# FMC_DAC_PSU.net
KiCad netlist of a schematic drawn in Altium Designer
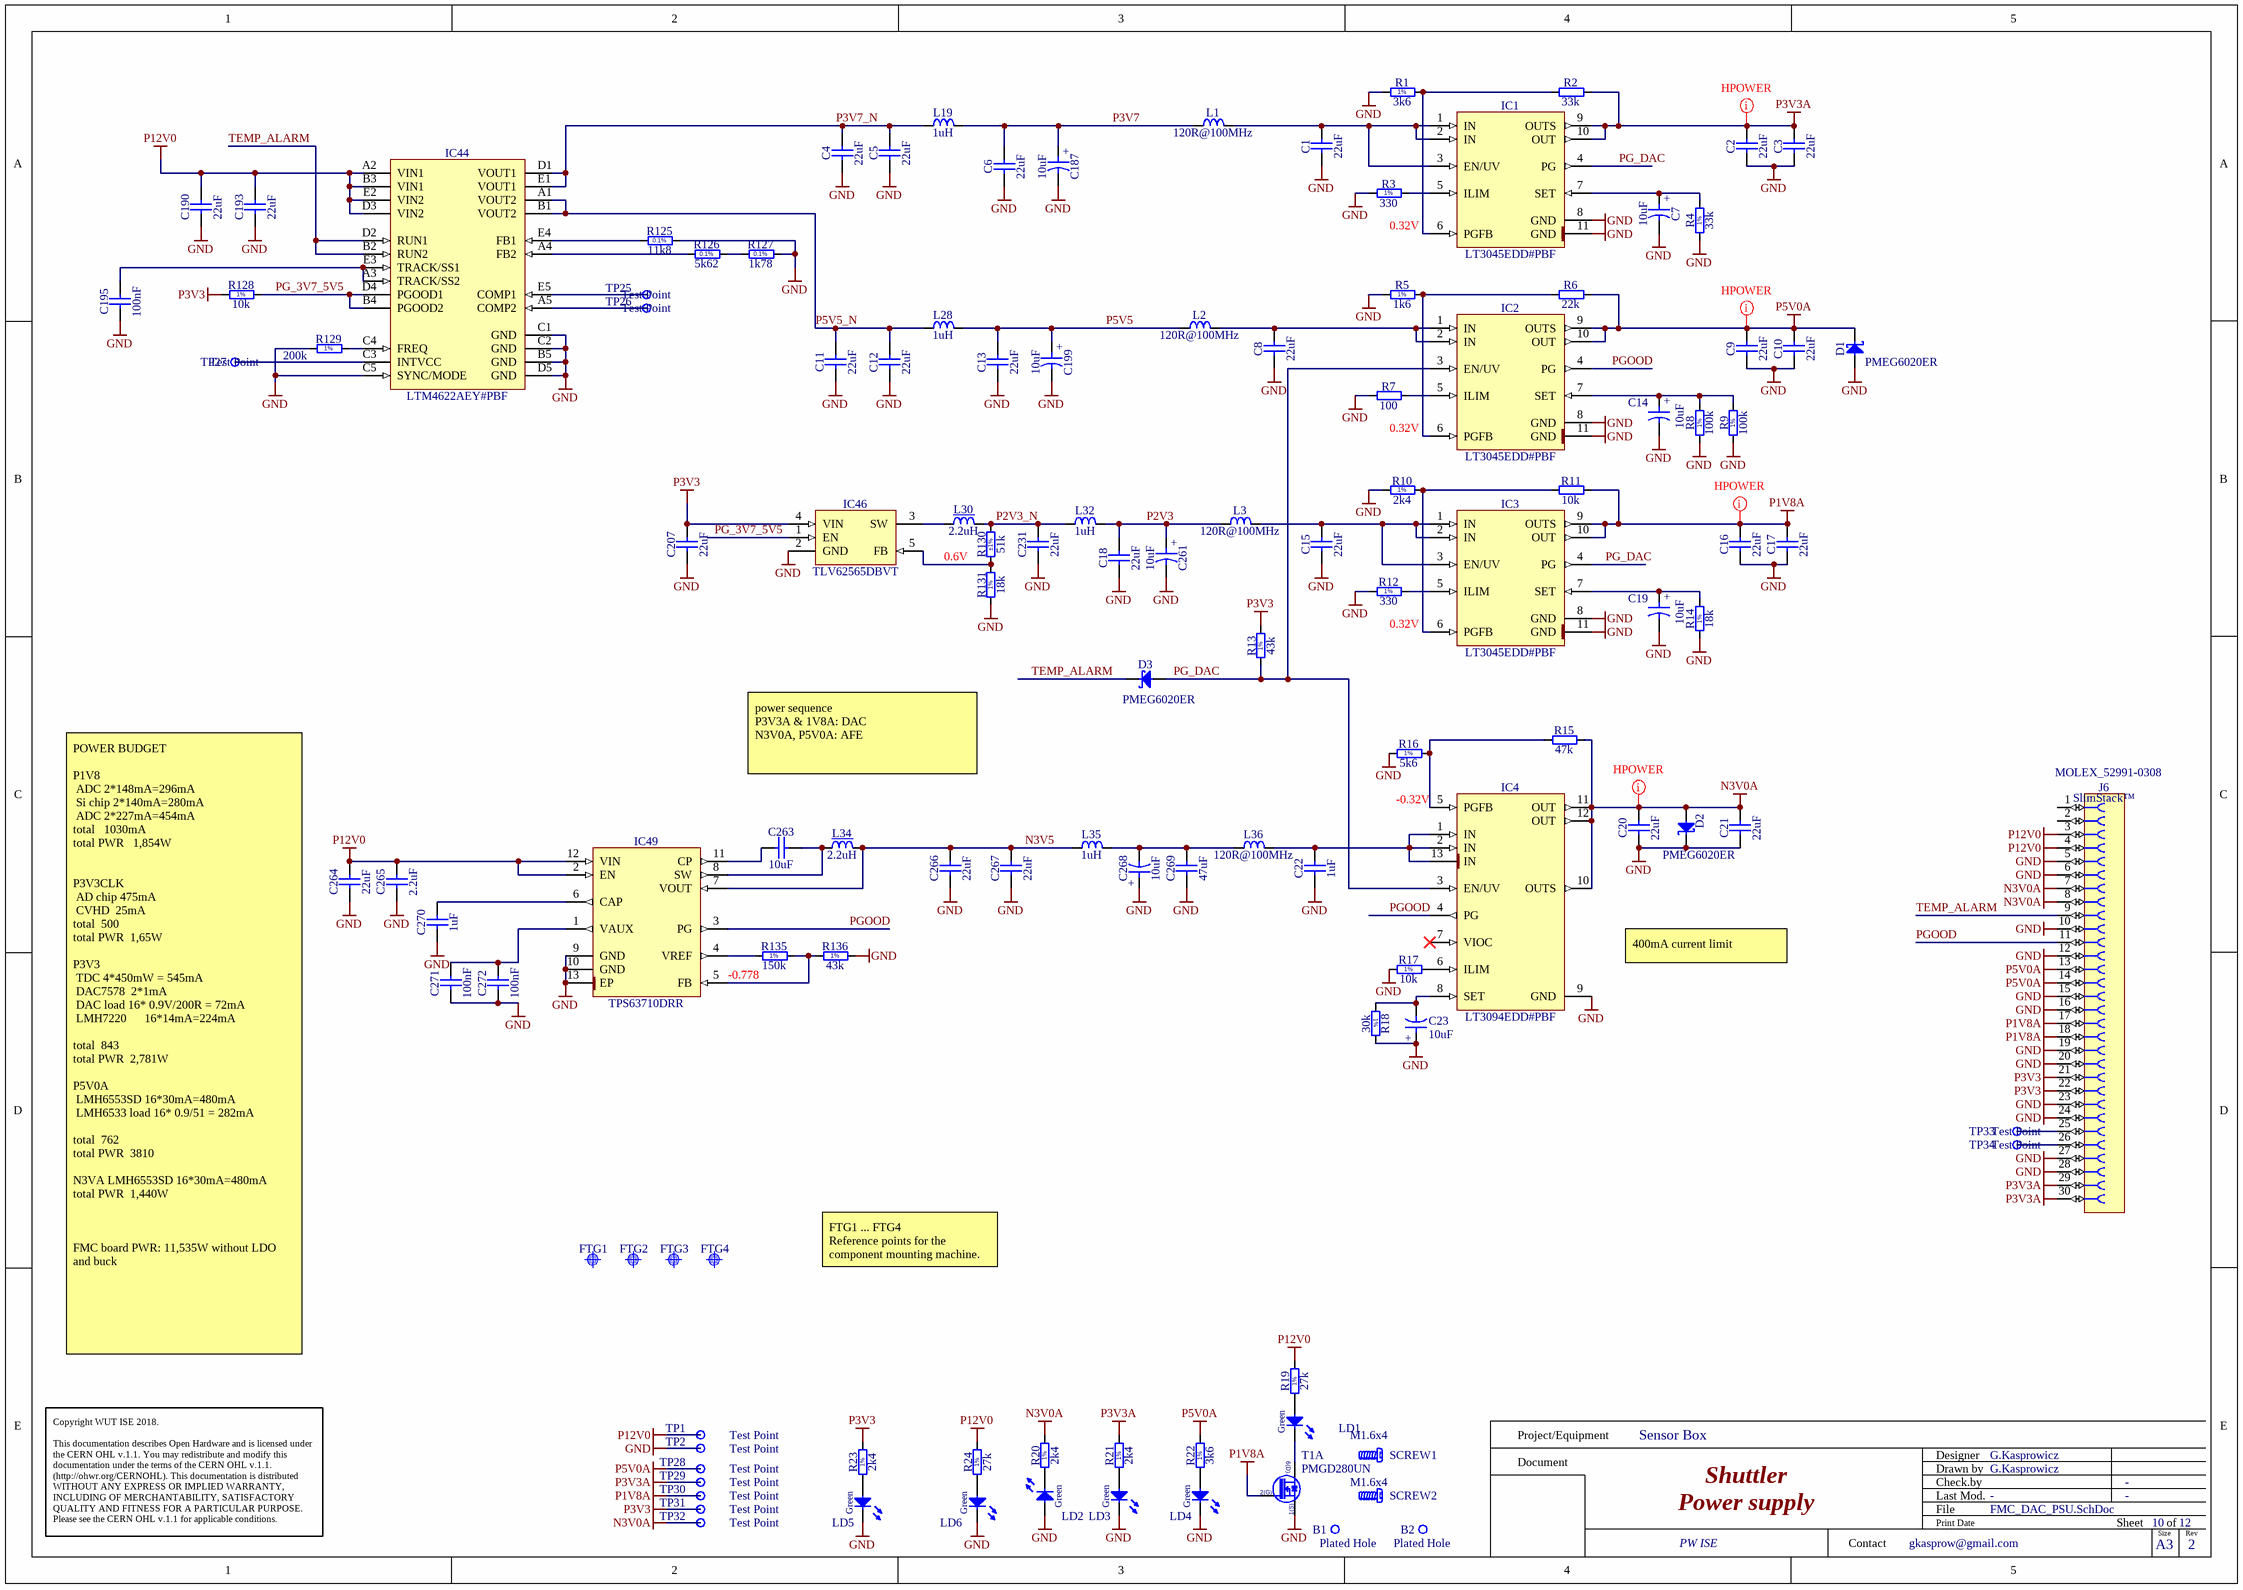
[diagram p0: FMC_DAC_PSU.SchDoc]

(export (version "E")
  (design (tool "Eeschema 10.0.6"))
  (components
    (comp (ref "B1")
      (value "Plated Hole")
      (footprint "c300h160")
      (description "Single Terminal Socket")
      (fields (field (name "PART NUMBER") "PLATED_HOLE1.6_PAD3.0") (field (name "AUTHOR") "CERN DEM JMW"))
      (libsource (lib "Eletro-mechanical") (part "Single Terminal Socket"))
    )
    (comp (ref "B2")
      (value "Plated Hole")
      (footprint "c300h160")
      (description "Single Terminal Socket")
      (fields (field (name "PART NUMBER") "PLATED_HOLE1.6_PAD3.0") (field (name "AUTHOR") "CERN DEM JMW"))
      (libsource (lib "Eletro-mechanical") (part "Single Terminal Socket"))
    )
    (comp (ref "C1")
      (value "22uF")
      (footprint "CAPC2012X135N")
      (description "Non-polarised capacitor")
      (fields
        (field (name "PART NUMBER") "CC0805_22UF_16V_10%_X5R")
        (field (name "VOLTAGE") "16V")
        (field (name "AUTHOR") "CERN DEM JLC")
      )
      (libsource (lib "Capacitors") (part "Capacitor - non polarized"))
    )
    (comp (ref "C2")
      (value "22uF")
      (footprint "CAPC2012X135N")
      (description "Non-polarised capacitor")
      (fields
        (field (name "PART NUMBER") "CC0805_22UF_16V_10%_X5R")
        (field (name "VOLTAGE") "16V")
        (field (name "AUTHOR") "CERN DEM JLC")
      )
      (libsource (lib "Capacitors") (part "Capacitor - non polarized"))
    )
    (comp (ref "C3")
      (value "22uF")
      (footprint "CAPC2012X135N")
      (description "Non-polarised capacitor")
      (fields
        (field (name "PART NUMBER") "CC0805_22UF_16V_10%_X5R")
        (field (name "VOLTAGE") "16V")
        (field (name "AUTHOR") "CERN DEM JLC")
      )
      (libsource (lib "Capacitors") (part "Capacitor - non polarized"))
    )
    (comp (ref "C4")
      (value "22uF")
      (footprint "CAPC2012X135N")
      (description "Non-polarised capacitor")
      (fields
        (field (name "PART NUMBER") "CC0805_22UF_16V_10%_X5R")
        (field (name "VOLTAGE") "16V")
        (field (name "AUTHOR") "CERN DEM JLC")
      )
      (libsource (lib "Capacitors") (part "Capacitor - non polarized"))
    )
    (comp (ref "C5")
      (value "22uF")
      (footprint "CAPC2012X135N")
      (description "Non-polarised capacitor")
      (fields
        (field (name "PART NUMBER") "CC0805_22UF_16V_10%_X5R")
        (field (name "VOLTAGE") "16V")
        (field (name "AUTHOR") "CERN DEM JLC")
      )
      (libsource (lib "Capacitors") (part "Capacitor - non polarized"))
    )
    (comp (ref "C6")
      (value "22uF")
      (footprint "CAPC2012X135N")
      (description "Non-polarised capacitor")
      (fields
        (field (name "PART NUMBER") "CC0805_22UF_16V_10%_X5R")
        (field (name "VOLTAGE") "16V")
        (field (name "AUTHOR") "CERN DEM JLC")
      )
      (libsource (lib "Capacitors") (part "Capacitor - non polarized"))
    )
    (comp (ref "C7")
      (value "10uF")
      (footprint "CAPMP3216X180N")
      (description "Polarised capacitor")
      (fields
        (field (name "PART NUMBER") "CTE3216-18_10UF_16V_20%_AVX_TCJ")
        (field (name "VOLTAGE") "16V")
        (field (name "AUTHOR") "CERN DEM JLC")
      )
      (libsource (lib "Capacitors") (part "Capacitor - polarized"))
    )
    (comp (ref "C8")
      (value "22uF")
      (footprint "CAPC2012X135N")
      (description "Non-polarised capacitor")
      (fields
        (field (name "PART NUMBER") "CC0805_22UF_16V_10%_X5R")
        (field (name "VOLTAGE") "16V")
        (field (name "AUTHOR") "CERN DEM JLC")
      )
      (libsource (lib "Capacitors") (part "Capacitor - non polarized"))
    )
    (comp (ref "C9")
      (value "22uF")
      (footprint "CAPC2012X135N")
      (description "Non-polarised capacitor")
      (fields
        (field (name "PART NUMBER") "CC0805_22UF_16V_10%_X5R")
        (field (name "VOLTAGE") "16V")
        (field (name "AUTHOR") "CERN DEM JLC")
      )
      (libsource (lib "Capacitors") (part "Capacitor - non polarized"))
    )
    (comp (ref "C10")
      (value "22uF")
      (footprint "CAPC2012X135N")
      (description "Non-polarised capacitor")
      (fields
        (field (name "PART NUMBER") "CC0805_22UF_16V_10%_X5R")
        (field (name "VOLTAGE") "16V")
        (field (name "AUTHOR") "CERN DEM JLC")
      )
      (libsource (lib "Capacitors") (part "Capacitor - non polarized"))
    )
    (comp (ref "C11")
      (value "22uF")
      (footprint "CAPC2012X135N")
      (description "Non-polarised capacitor")
      (fields
        (field (name "PART NUMBER") "CC0805_22UF_16V_10%_X5R")
        (field (name "VOLTAGE") "16V")
        (field (name "AUTHOR") "CERN DEM JLC")
      )
      (libsource (lib "Capacitors") (part "Capacitor - non polarized"))
    )
    (comp (ref "C12")
      (value "22uF")
      (footprint "CAPC2012X135N")
      (description "Non-polarised capacitor")
      (fields
        (field (name "PART NUMBER") "CC0805_22UF_16V_10%_X5R")
        (field (name "VOLTAGE") "16V")
        (field (name "AUTHOR") "CERN DEM JLC")
      )
      (libsource (lib "Capacitors") (part "Capacitor - non polarized"))
    )
    (comp (ref "C13")
      (value "22uF")
      (footprint "CAPC2012X135N")
      (description "Non-polarised capacitor")
      (fields
        (field (name "PART NUMBER") "CC0805_22UF_16V_10%_X5R")
        (field (name "VOLTAGE") "16V")
        (field (name "AUTHOR") "CERN DEM JLC")
      )
      (libsource (lib "Capacitors") (part "Capacitor - non polarized"))
    )
    (comp (ref "C14")
      (value "10uF")
      (footprint "CAPMP3216X180N")
      (description "Polarised capacitor")
      (fields
        (field (name "PART NUMBER") "CTE3216-18_10UF_16V_20%_AVX_TCJ")
        (field (name "VOLTAGE") "16V")
        (field (name "AUTHOR") "CERN DEM JLC")
      )
      (libsource (lib "Capacitors") (part "Capacitor - polarized"))
    )
    (comp (ref "C15")
      (value "22uF")
      (footprint "CAPC2012X135N")
      (description "Non-polarised capacitor")
      (fields
        (field (name "PART NUMBER") "CC0805_22UF_16V_10%_X5R")
        (field (name "VOLTAGE") "16V")
        (field (name "AUTHOR") "CERN DEM JLC")
      )
      (libsource (lib "Capacitors") (part "Capacitor - non polarized"))
    )
    (comp (ref "C16")
      (value "22uF")
      (footprint "CAPC2012X135N")
      (description "Non-polarised capacitor")
      (fields
        (field (name "PART NUMBER") "CC0805_22UF_16V_10%_X5R")
        (field (name "VOLTAGE") "16V")
        (field (name "AUTHOR") "CERN DEM JLC")
      )
      (libsource (lib "Capacitors") (part "Capacitor - non polarized"))
    )
    (comp (ref "C17")
      (value "22uF")
      (footprint "CAPC2012X135N")
      (description "Non-polarised capacitor")
      (fields
        (field (name "PART NUMBER") "CC0805_22UF_16V_10%_X5R")
        (field (name "VOLTAGE") "16V")
        (field (name "AUTHOR") "CERN DEM JLC")
      )
      (libsource (lib "Capacitors") (part "Capacitor - non polarized"))
    )
    (comp (ref "C18")
      (value "22uF")
      (footprint "CAPC2012X135N")
      (description "Non-polarised capacitor")
      (fields
        (field (name "PART NUMBER") "CC0805_22UF_16V_10%_X5R")
        (field (name "VOLTAGE") "16V")
        (field (name "AUTHOR") "CERN DEM JLC")
      )
      (libsource (lib "Capacitors") (part "Capacitor - non polarized"))
    )
    (comp (ref "C19")
      (value "10uF")
      (footprint "CAPMP3216X180N")
      (description "Polarised capacitor")
      (fields
        (field (name "PART NUMBER") "CTE3216-18_10UF_16V_20%_AVX_TCJ")
        (field (name "VOLTAGE") "16V")
        (field (name "AUTHOR") "CERN DEM JLC")
      )
      (libsource (lib "Capacitors") (part "Capacitor - polarized"))
    )
    (comp (ref "C20")
      (value "22uF")
      (footprint "CAPC2012X135N")
      (description "Non-polarised capacitor")
      (fields
        (field (name "PART NUMBER") "CC0805_22UF_16V_10%_X5R")
        (field (name "VOLTAGE") "16V")
        (field (name "AUTHOR") "CERN DEM JLC")
      )
      (libsource (lib "Capacitors") (part "Capacitor - non polarized"))
    )
    (comp (ref "C21")
      (value "22uF")
      (footprint "CAPC2012X135N")
      (description "Non-polarised capacitor")
      (fields
        (field (name "PART NUMBER") "CC0805_22UF_16V_10%_X5R")
        (field (name "VOLTAGE") "16V")
        (field (name "AUTHOR") "CERN DEM JLC")
      )
      (libsource (lib "Capacitors") (part "Capacitor - non polarized"))
    )
    (comp (ref "C22")
      (value "1uF")
      (footprint "CAPC1608X87N")
      (description "Non-polarised capacitor")
      (fields
        (field (name "PART NUMBER") "CC0603_1UF_25V_10%_X7R")
        (field (name "VOLTAGE") "25V")
        (field (name "AUTHOR") "CERN DEM JLC")
      )
      (libsource (lib "Capacitors") (part "Capacitor - non polarized"))
    )
    (comp (ref "C23")
      (value "10uF")
      (footprint "CAPMP3216X180N")
      (description "Polarised capacitor")
      (fields
        (field (name "PART NUMBER") "CTE3216-18_10UF_16V_20%_AVX_TCJ")
        (field (name "VOLTAGE") "16V")
        (field (name "AUTHOR") "CERN DEM JLC")
      )
      (libsource (lib "Capacitors") (part "Capacitor - polarized"))
    )
    (comp (ref "C187")
      (value "10uF")
      (footprint "CAPMP3216X180N")
      (description "Polarised capacitor")
      (fields
        (field (name "PART NUMBER") "CTE3216-18_10UF_10V_10%_LESR1800")
        (field (name "VOLTAGE") "10V")
        (field (name "AUTHOR") "CERN DEM JLC")
      )
      (libsource (lib "Capacitors") (part "Capacitor - polarized"))
    )
    (comp (ref "C190")
      (value "22uF")
      (footprint "CAPC2012X135N")
      (description "Non-polarised capacitor")
      (fields
        (field (name "PART NUMBER") "CC0805_22UF_16V_10%_X5R")
        (field (name "VOLTAGE") "16V")
        (field (name "AUTHOR") "CERN DEM JLC")
      )
      (libsource (lib "Capacitors") (part "Capacitor - non polarized"))
    )
    (comp (ref "C193")
      (value "22uF")
      (footprint "CAPC2012X135N")
      (description "Non-polarised capacitor")
      (fields
        (field (name "PART NUMBER") "CC0805_22UF_16V_10%_X5R")
        (field (name "VOLTAGE") "16V")
        (field (name "AUTHOR") "CERN DEM JLC")
      )
      (libsource (lib "Capacitors") (part "Capacitor - non polarized"))
    )
    (comp (ref "C195")
      (value "100nF")
      (footprint "CAPC1005X55N")
      (description "Non-polarised capacitor")
      (fields
        (field (name "PART NUMBER") "CC0402_100NF_16V_10%_X5R")
        (field (name "VOLTAGE") "16V")
        (field (name "AUTHOR") "CERN DEM JLC")
      )
      (libsource (lib "Capacitors") (part "Capacitor - non polarized"))
    )
    (comp (ref "C199")
      (value "10uF")
      (footprint "CAPMP3216X180N")
      (description "Polarised capacitor")
      (fields
        (field (name "PART NUMBER") "CTE3216-18_10UF_10V_10%_LESR1800")
        (field (name "VOLTAGE") "10V")
        (field (name "AUTHOR") "CERN DEM JLC")
      )
      (libsource (lib "Capacitors") (part "Capacitor - polarized"))
    )
    (comp (ref "C207")
      (value "22uF")
      (footprint "CAPC2012X135N")
      (description "Non-polarised capacitor")
      (fields
        (field (name "PART NUMBER") "CC0805_22UF_16V_10%_X5R")
        (field (name "VOLTAGE") "16V")
        (field (name "AUTHOR") "CERN DEM JLC")
      )
      (libsource (lib "Capacitors") (part "Capacitor - non polarized"))
    )
    (comp (ref "C231")
      (value "22uF")
      (footprint "CAPC2012X135N")
      (description "Non-polarised capacitor")
      (fields
        (field (name "PART NUMBER") "CC0805_22UF_16V_10%_X5R")
        (field (name "VOLTAGE") "16V")
        (field (name "AUTHOR") "CERN DEM JLC")
      )
      (libsource (lib "Capacitors") (part "Capacitor - non polarized"))
    )
    (comp (ref "C261")
      (value "10uF")
      (footprint "CAPMP3216X180N")
      (description "Polarised capacitor")
      (fields
        (field (name "PART NUMBER") "CTE3216-18_10UF_10V_10%_LESR1800")
        (field (name "VOLTAGE") "10V")
        (field (name "AUTHOR") "CERN DEM JLC")
      )
      (libsource (lib "Capacitors") (part "Capacitor - polarized"))
    )
    (comp (ref "C263")
      (value "10uF")
      (footprint "CAPC2012X135N")
      (description "Non-polarised capacitor")
      (fields
        (field (name "PART NUMBER") "CC0805_10UF_16V_10%_X5R")
        (field (name "VOLTAGE") "16V")
        (field (name "AUTHOR") "CERN DEM JLC")
      )
      (libsource (lib "Capacitors") (part "Capacitor - non polarized"))
    )
    (comp (ref "C264")
      (value "22uF")
      (footprint "CAPC2012X135N")
      (description "Non-polarised capacitor")
      (fields
        (field (name "PART NUMBER") "CC0805_22UF_16V_10%_X5R")
        (field (name "VOLTAGE") "16V")
        (field (name "AUTHOR") "CERN DEM JLC")
      )
      (libsource (lib "Capacitors") (part "Capacitor - non polarized"))
    )
    (comp (ref "C265")
      (value "2.2uF")
      (footprint "CAPC1608X87N")
      (description "Non-polarised capacitor")
      (fields
        (field (name "PART NUMBER") "CC0603_2.2UF_16V_10%_X5R")
        (field (name "VOLTAGE") "16V")
        (field (name "AUTHOR") "CERN DEM JLC")
      )
      (libsource (lib "Capacitors") (part "Capacitor - non polarized"))
    )
    (comp (ref "C266")
      (value "22uF")
      (footprint "CAPC2012X135N")
      (description "Non-polarised capacitor")
      (fields
        (field (name "PART NUMBER") "CC0805_22UF_16V_10%_X5R")
        (field (name "VOLTAGE") "16V")
        (field (name "AUTHOR") "CERN DEM JLC")
      )
      (libsource (lib "Capacitors") (part "Capacitor - non polarized"))
    )
    (comp (ref "C267")
      (value "22uF")
      (footprint "CAPC2012X135N")
      (description "Non-polarised capacitor")
      (fields
        (field (name "PART NUMBER") "CC0805_22UF_16V_10%_X5R")
        (field (name "VOLTAGE") "16V")
        (field (name "AUTHOR") "CERN DEM JLC")
      )
      (libsource (lib "Capacitors") (part "Capacitor - non polarized"))
    )
    (comp (ref "C268")
      (value "10uF")
      (footprint "CAPMP3216X180N")
      (description "Polarised capacitor")
      (fields
        (field (name "PART NUMBER") "CTE3216-18_10UF_10V_10%_LESR1800")
        (field (name "VOLTAGE") "10V")
        (field (name "AUTHOR") "CERN DEM JLC")
      )
      (libsource (lib "Capacitors") (part "Capacitor - polarized"))
    )
    (comp (ref "C269")
      (value "47uF")
      (footprint "CAPC2012X140N")
      (description "Non-polarised capacitor")
      (fields
        (field (name "PART NUMBER") "CC0805_47UF_6.3V_20%_X5R")
        (field (name "VOLTAGE") "6.3V")
        (field (name "AUTHOR") "CERN DEM JLC")
      )
      (libsource (lib "Capacitors") (part "Capacitor - non polarized"))
    )
    (comp (ref "C270")
      (value "1uF")
      (footprint "CAPC1608X87N")
      (description "Non-polarised capacitor")
      (fields
        (field (name "PART NUMBER") "CC0603_1UF_16V_10%_X7R")
        (field (name "VOLTAGE") "16V")
        (field (name "AUTHOR") "CERN DEM JLC")
      )
      (libsource (lib "Capacitors") (part "Capacitor - non polarized"))
    )
    (comp (ref "C271")
      (value "100nF")
      (footprint "CAPC1005X55N")
      (description "Non-polarised capacitor")
      (fields
        (field (name "PART NUMBER") "CC0402_100NF_16V_10%_X5R")
        (field (name "VOLTAGE") "16V")
        (field (name "AUTHOR") "CERN DEM JLC")
      )
      (libsource (lib "Capacitors") (part "Capacitor - non polarized"))
    )
    (comp (ref "C272")
      (value "100nF")
      (footprint "CAPC1005X55N")
      (description "Non-polarised capacitor")
      (fields
        (field (name "PART NUMBER") "CC0402_100NF_16V_10%_X5R")
        (field (name "VOLTAGE") "16V")
        (field (name "AUTHOR") "CERN DEM JLC")
      )
      (libsource (lib "Capacitors") (part "Capacitor - non polarized"))
    )
    (comp (ref "D1")
      (value "PMEG6020ER")
      (footprint "SODFL3517X110N")
      (description "Schottky Diode")
      (fields
        (field (name "VOLTAGE") "60V")
        (field (name "POWER") "2A")
        (field (name "AUTHOR") "CERN DEM JMW")
      )
      (libsource (lib "ICs And Semiconductors") (part "Diode Schottky"))
    )
    (comp (ref "D2")
      (value "PMEG6020ER")
      (footprint "SODFL3517X110N")
      (description "Schottky Diode")
      (fields
        (field (name "VOLTAGE") "60V")
        (field (name "POWER") "2A")
        (field (name "AUTHOR") "CERN DEM JMW")
      )
      (libsource (lib "ICs And Semiconductors") (part "Diode Schottky"))
    )
    (comp (ref "D3")
      (value "PMEG6020ER")
      (footprint "SODFL3517X110N")
      (description "Schottky Diode")
      (fields
        (field (name "VOLTAGE") "60V")
        (field (name "POWER") "2A")
        (field (name "AUTHOR") "CERN DEM JMW")
      )
      (libsource (lib "ICs And Semiconductors") (part "Diode Schottky"))
    )
    (comp (ref "FTG1")
      (value "Use only in PCB")
      (footprint "FIDUCIAL_TOP_S100-200")
      (description "Fiducial Target")
      (fields (field (name "PART NUMBER") "FIDUCIAL_TARGET_S100-200") (field (name "AUTHOR") "CERN DEM JLC"))
      (libsource (lib "Eletro-mechanical") (part "Fiducial Target"))
    )
    (comp (ref "FTG2")
      (value "Use only in PCB")
      (footprint "FIDUCIAL_TOP_C100-200")
      (description "Fiducial Target")
      (fields (field (name "PART NUMBER") "FIDUCIAL_TARGET_C100-200") (field (name "AUTHOR") "CERN DEM JLC"))
      (libsource (lib "Eletro-mechanical") (part "Fiducial Target"))
    )
    (comp (ref "FTG3")
      (value "Use only in PCB")
      (footprint "FIDUCIAL_TOP_S100-200")
      (description "Fiducial Target")
      (fields (field (name "PART NUMBER") "FIDUCIAL_TARGET_S100-200") (field (name "AUTHOR") "CERN DEM JLC"))
      (libsource (lib "Eletro-mechanical") (part "Fiducial Target"))
    )
    (comp (ref "FTG4")
      (value "Use only in PCB")
      (footprint "FIDUCIAL_TOP_C100-200")
      (description "Fiducial Target")
      (fields (field (name "PART NUMBER") "FIDUCIAL_TARGET_C100-200") (field (name "AUTHOR") "CERN DEM JLC"))
      (libsource (lib "Eletro-mechanical") (part "Fiducial Target"))
    )
    (comp (ref "IC1")
      (value "LT3045EDD#PBF")
      (footprint "SON50P300X300X80-11N-R175X248")
      (description "20V, 500mA, Ultralow Noise, Ultrahigh PSRR Linear Regulator")
      (fields (field (name "MANUFACTURER") "LINEAR TECHNOLOGY") (field (name "AUTHOR") "CERN DEM JLC"))
      (libsource (lib "ICs And Semiconductors") (part "LT3045EDD"))
    )
    (comp (ref "IC2")
      (value "LT3045EDD#PBF")
      (footprint "SON50P300X300X80-11N-R175X248")
      (description "20V, 500mA, Ultralow Noise, Ultrahigh PSRR Linear Regulator")
      (fields (field (name "MANUFACTURER") "LINEAR TECHNOLOGY") (field (name "AUTHOR") "CERN DEM JLC"))
      (libsource (lib "ICs And Semiconductors") (part "LT3045EDD"))
    )
    (comp (ref "IC3")
      (value "LT3045EDD#PBF")
      (footprint "SON50P300X300X80-11N-R175X248")
      (description "20V, 500mA, Ultralow Noise, Ultrahigh PSRR Linear Regulator")
      (fields (field (name "MANUFACTURER") "LINEAR TECHNOLOGY") (field (name "AUTHOR") "CERN DEM JLC"))
      (libsource (lib "ICs And Semiconductors") (part "LT3045EDD"))
    )
    (comp (ref "IC4")
      (value "LT3094EDD#PBF")
      (footprint "SON45P300X300X80-13N-R175X248")
      (description "-20V, 500mA, Ultralow Noise, Ultrahigh PSRR Negative Linear Regulator")
      (fields (field (name "MANUFACTURER") "LINEAR TECHNOLOGY") (field (name "AUTHOR") "CERN DEM JLC"))
      (libsource (lib "ICs And Semiconductors") (part "LT3094"))
    )
    (comp (ref "IC44")
      (value "LTM4622AEY#PBF")
      (footprint "BGA25C127P5X5_625X625X262")
      (description "3.6V-20V To 1.5V-12V, Dual 2A or Single 4A  Ultrathin Step-Down DC/DC µModule Regulator")
      (fields (field (name "MANUFACTURER") "LINEAR TECHNOLOGY") (field (name "AUTHOR") "CERN DEM MR"))
      (libsource (lib "ICs And Semiconductors") (part "LTM4622A"))
    )
    (comp (ref "IC46")
      (value "TLV62565DBVT")
      (footprint "SOT95P280X145-5N")
      (description "1.5A High Efficiency Step-Down Converter, Adjustable Output Voltage")
      (fields (field (name "MANUFACTURER") "TEXAS INSTRUMENTS") (field (name "AUTHOR") "CERN DEM JMW"))
      (libsource (lib "ICs And Semiconductors") (part "TLV62565"))
    )
    (comp (ref "IC49")
      (value "TPS63710DRR")
      (footprint "SON50P300X300X80-13N-R160X260")
      (description "-1 to -5.5VDC, 1A Output, Low Noise Synchronous Inverting Buck Converter")
      (fields (field (name "MANUFACTURER") "TEXAS INSTRUMENTS") (field (name "AUTHOR") "CERN DEM BC"))
      (libsource (lib "ICs And Semiconductors") (part "TPS63710"))
    )
    (comp (ref "J6")
      (value "SlimStack™")
      (footprint "MOLEX_52991-0308")
      (description "Connector 30 Female")
      (fields
        (field (name "PART NUMBER") "MOLEX_52991-0308")
        (field (name "MANUFACTURER") "MOLEX")
        (field (name "MANUFACTURER PART NUMBER") "52991-0308")
        (field (name "AUTHOR") "CERN DEM JLC")
      )
      (libsource (lib "Connectors") (part "Connector 30 Female"))
    )
    (comp (ref "L1")
      (value "120R@100MHz")
      (footprint "INDC1608X65N")
      (description "Inductor")
      (fields
        (field (name "PART NUMBER") "IND0603_MURATA_BLM18SG121TN1D")
        (field (name "POWER") "3A")
        (field (name "AUTHOR") "CERN DEM JLC")
      )
      (libsource (lib "Inductors & Transformers") (part "Inductor"))
    )
    (comp (ref "L2")
      (value "120R@100MHz")
      (footprint "INDC1608X65N")
      (description "Inductor")
      (fields
        (field (name "PART NUMBER") "IND0603_MURATA_BLM18SG121TN1D")
        (field (name "POWER") "3A")
        (field (name "AUTHOR") "CERN DEM JLC")
      )
      (libsource (lib "Inductors & Transformers") (part "Inductor"))
    )
    (comp (ref "L3")
      (value "120R@100MHz")
      (footprint "INDC1608X65N")
      (description "Inductor")
      (fields
        (field (name "PART NUMBER") "IND0603_MURATA_BLM18SG121TN1D")
        (field (name "POWER") "3A")
        (field (name "AUTHOR") "CERN DEM JLC")
      )
      (libsource (lib "Inductors & Transformers") (part "Inductor"))
    )
    (comp (ref "L19")
      (value "1uH")
      (footprint "INDC2620X100N")
      (description "Inductor")
      (fields
        (field (name "PART NUMBER") "IND1008_1UH_20%_WURTH_74479787210B")
        (field (name "POWER") "1.95A")
        (field (name "AUTHOR") "CERN DEM JLC")
      )
      (libsource (lib "Inductors & Transformers") (part "Inductor"))
    )
    (comp (ref "L28")
      (value "1uH")
      (footprint "INDC2620X100N")
      (description "Inductor")
      (fields
        (field (name "PART NUMBER") "IND1008_1UH_20%_WURTH_74479787210B")
        (field (name "POWER") "1.95A")
        (field (name "AUTHOR") "CERN DEM JLC")
      )
      (libsource (lib "Inductors & Transformers") (part "Inductor"))
    )
    (comp (ref "L30")
      (value "2.2uH")
      (footprint "IND_WURTH_WE-TPC_4828")
      (description "Inductor With Core")
      (fields
        (field (name "PART NUMBER") "IND_2.2UH_30%_WURTH_WE-TPC_7440430022")
        (field (name "POWER") "2.5A")
        (field (name "AUTHOR") "CERN DEM JLC")
      )
      (libsource (lib "Inductors & Transformers") (part "Inductor With Magnetic core"))
    )
    (comp (ref "L32")
      (value "1uH")
      (footprint "INDC2620X100N")
      (description "Inductor")
      (fields
        (field (name "PART NUMBER") "IND1008_1UH_20%_WURTH_74479787210B")
        (field (name "POWER") "1.95A")
        (field (name "AUTHOR") "CERN DEM JLC")
      )
      (libsource (lib "Inductors & Transformers") (part "Inductor"))
    )
    (comp (ref "L34")
      (value "2.2uH")
      (footprint "IND_WURTH_WE-TPC_4828")
      (description "Inductor With Core")
      (fields
        (field (name "PART NUMBER") "IND_2.2UH_30%_WURTH_WE-TPC_7440430022")
        (field (name "POWER") "2.5A")
        (field (name "AUTHOR") "CERN DEM JLC")
      )
      (libsource (lib "Inductors & Transformers") (part "Inductor With Magnetic core"))
    )
    (comp (ref "L35")
      (value "1uH")
      (footprint "INDC2620X100N")
      (description "Inductor")
      (fields
        (field (name "PART NUMBER") "IND1008_1UH_20%_WURTH_74479787210B")
        (field (name "POWER") "1.95A")
        (field (name "AUTHOR") "CERN DEM JLC")
      )
      (libsource (lib "Inductors & Transformers") (part "Inductor"))
    )
    (comp (ref "L36")
      (value "120R@100MHz")
      (footprint "INDC1608X65N")
      (description "Inductor")
      (fields
        (field (name "PART NUMBER") "IND0603_MURATA_BLM18SG121TN1D")
        (field (name "POWER") "3A")
        (field (name "AUTHOR") "CERN DEM JLC")
      )
      (libsource (lib "Inductors & Transformers") (part "Inductor"))
    )
    (comp (ref "LD1")
      (value "Green")
      (footprint "LED_KINGBRIGHT_KPH-1608CGCK")
      (description "LED Green 1C 2A")
      (fields
        (field (name "PART NUMBER") "LED_KINGBRIGHT_KPH-1608CGCK")
        (field (name "MANUFACTURER") "KINGBRIGHT")
        (field (name "AUTHOR") "CERN DEM JLC")
      )
      (libsource (lib "ICs And Semiconductors") (part "LED Green 1C 2A"))
    )
    (comp (ref "LD2")
      (value "Green")
      (footprint "LED_KINGBRIGHT_KPH-1608CGCK")
      (description "LED Green 1C 2A")
      (fields
        (field (name "PART NUMBER") "LED_KINGBRIGHT_KPH-1608CGCK")
        (field (name "MANUFACTURER") "KINGBRIGHT")
        (field (name "AUTHOR") "CERN DEM JLC")
      )
      (libsource (lib "ICs And Semiconductors") (part "LED Green 1C 2A"))
    )
    (comp (ref "LD3")
      (value "Green")
      (footprint "LED_KINGBRIGHT_KPH-1608CGCK")
      (description "LED Green 1C 2A")
      (fields
        (field (name "PART NUMBER") "LED_KINGBRIGHT_KPH-1608CGCK")
        (field (name "MANUFACTURER") "KINGBRIGHT")
        (field (name "AUTHOR") "CERN DEM JLC")
      )
      (libsource (lib "ICs And Semiconductors") (part "LED Green 1C 2A"))
    )
    (comp (ref "LD4")
      (value "Green")
      (footprint "LED_KINGBRIGHT_KPH-1608CGCK")
      (description "LED Green 1C 2A")
      (fields
        (field (name "PART NUMBER") "LED_KINGBRIGHT_KPH-1608CGCK")
        (field (name "MANUFACTURER") "KINGBRIGHT")
        (field (name "AUTHOR") "CERN DEM JLC")
      )
      (libsource (lib "ICs And Semiconductors") (part "LED Green 1C 2A"))
    )
    (comp (ref "LD5")
      (value "Green")
      (footprint "LED_KINGBRIGHT_KPH-1608CGCK")
      (description "LED Green 1C 2A")
      (fields
        (field (name "PART NUMBER") "LED_KINGBRIGHT_KPH-1608CGCK")
        (field (name "MANUFACTURER") "KINGBRIGHT")
        (field (name "AUTHOR") "CERN DEM JLC")
      )
      (libsource (lib "ICs And Semiconductors") (part "LED Green 1C 2A"))
    )
    (comp (ref "LD6")
      (value "Green")
      (footprint "LED_KINGBRIGHT_KPH-1608CGCK")
      (description "LED Green 1C 2A")
      (fields
        (field (name "PART NUMBER") "LED_KINGBRIGHT_KPH-1608CGCK")
        (field (name "MANUFACTURER") "KINGBRIGHT")
        (field (name "AUTHOR") "CERN DEM JLC")
      )
      (libsource (lib "ICs And Semiconductors") (part "LED Green 1C 2A"))
    )
    (comp (ref "R1")
      (value "3k6")
      (footprint "RESC1005X40N")
      (description "Resistor - 1%")
      (fields
        (field (name "PART NUMBER") "R0402_3K6_1%_0.0625W_100PPM")
        (field (name "POWER") "0.0625W")
        (field (name "AUTHOR") "CERN DEM JLC")
      )
      (libsource (lib "Resistors") (part "Resistor - 1%"))
    )
    (comp (ref "R2")
      (value "33k")
      (footprint "RESC1005X40N")
      (description "Resistor - 1%")
      (fields
        (field (name "PART NUMBER") "R0402_33K_1%_0.0625W_100PPM")
        (field (name "POWER") "0.0625W")
        (field (name "AUTHOR") "CERN DEM JLC")
      )
      (libsource (lib "Resistors") (part "Resistor - 1%"))
    )
    (comp (ref "R3")
      (value "330")
      (footprint "RESC1005X40N")
      (description "Resistor - 1%")
      (fields
        (field (name "PART NUMBER") "R0402_330R_1%_0.0625W_100PPM")
        (field (name "POWER") "0.0625W")
        (field (name "AUTHOR") "CERN DEM JLC")
      )
      (libsource (lib "Resistors") (part "Resistor - 1%"))
    )
    (comp (ref "R4")
      (value "33k")
      (footprint "RESC1608X55N")
      (description "Resistor - 1%")
      (fields
        (field (name "PART NUMBER") "R0603_33K_1%_0.1W_100PPM")
        (field (name "POWER") "0.1W")
        (field (name "AUTHOR") "CERN DEM JLC")
      )
      (libsource (lib "Resistors") (part "Resistor - 1%"))
    )
    (comp (ref "R5")
      (value "1k6")
      (footprint "RESC1005X40N")
      (description "Resistor - 1%")
      (fields
        (field (name "PART NUMBER") "R0402_1K6_1%_0.0625W_100PPM")
        (field (name "POWER") "0.0625W")
        (field (name "AUTHOR") "CERN DEM JLC")
      )
      (libsource (lib "Resistors") (part "Resistor - 1%"))
    )
    (comp (ref "R6")
      (value "22k")
      (footprint "RESC1005X40N")
      (description "Resistor - 1%")
      (fields
        (field (name "PART NUMBER") "R0402_22K_1%_0.0625W_100PPM")
        (field (name "POWER") "0.0625W")
        (field (name "AUTHOR") "CERN DEM JLC")
      )
      (libsource (lib "Resistors") (part "Resistor - 1%"))
    )
    (comp (ref "R7")
      (value "100")
      (footprint "RESC1005X40N")
      (description "Resistor - 1%")
      (fields
        (field (name "PART NUMBER") "R0402_100R_1%_0.0625W_100PPM")
        (field (name "POWER") "0.0625W")
        (field (name "AUTHOR") "CERN DEM JLC")
      )
      (libsource (lib "Resistors") (part "Resistor - 1%"))
    )
    (comp (ref "R8")
      (value "100k")
      (footprint "RESC1005X40N")
      (description "Resistor - 1%")
      (fields
        (field (name "PART NUMBER") "R0402_100K_1%_0.0625W_100PPM")
        (field (name "POWER") "0.0625W")
        (field (name "AUTHOR") "CERN DEM JLC")
      )
      (libsource (lib "Resistors") (part "Resistor - 1%"))
    )
    (comp (ref "R9")
      (value "100k")
      (footprint "RESC1005X40N")
      (description "Resistor - 1%")
      (fields
        (field (name "PART NUMBER") "R0402_100K_1%_0.0625W_100PPM")
        (field (name "POWER") "0.0625W")
        (field (name "AUTHOR") "CERN DEM JLC")
      )
      (libsource (lib "Resistors") (part "Resistor - 1%"))
    )
    (comp (ref "R10")
      (value "2k4")
      (footprint "RESC1005X40N")
      (description "Resistor - 1%")
      (fields
        (field (name "PART NUMBER") "R0402_2K4_1%_0.0625W_100PPM")
        (field (name "POWER") "0.0625W")
        (field (name "AUTHOR") "CERN DEM JLC")
      )
      (libsource (lib "Resistors") (part "Resistor - 1%"))
    )
    (comp (ref "R11")
      (value "10k")
      (footprint "RESC1005X40N")
      (description "Resistor - 1%")
      (fields
        (field (name "PART NUMBER") "R0402_10K_1%_0.0625W_100PPM")
        (field (name "POWER") "0.0625W")
        (field (name "AUTHOR") "CERN DEM JLC")
      )
      (libsource (lib "Resistors") (part "Resistor - 1%"))
    )
    (comp (ref "R12")
      (value "330")
      (footprint "RESC1005X40N")
      (description "Resistor - 1%")
      (fields
        (field (name "PART NUMBER") "R0402_330R_1%_0.0625W_100PPM")
        (field (name "POWER") "0.0625W")
        (field (name "AUTHOR") "CERN DEM JLC")
      )
      (libsource (lib "Resistors") (part "Resistor - 1%"))
    )
    (comp (ref "R13")
      (value "43k")
      (footprint "RESC1005X40N")
      (description "Resistor - 1%")
      (fields
        (field (name "PART NUMBER") "R0402_43K_1%_0.0625W_100PPM")
        (field (name "POWER") "0.0625W")
        (field (name "AUTHOR") "CERN DEM JLC")
      )
      (libsource (lib "Resistors") (part "Resistor - 1%"))
    )
    (comp (ref "R14")
      (value "18k")
      (footprint "RESC1608X55N")
      (description "Resistor - 1%")
      (fields
        (field (name "PART NUMBER") "R0603_18K_1%_0.1W_100PPM")
        (field (name "POWER") "0.1W")
        (field (name "AUTHOR") "CERN DEM JLC")
      )
      (libsource (lib "Resistors") (part "Resistor - 1%"))
    )
    (comp (ref "R15")
      (value "47k")
      (footprint "RESC1005X40N")
      (description "Resistor - 1%")
      (fields
        (field (name "PART NUMBER") "R0402_47K_1%_0.0625W_100PPM")
        (field (name "POWER") "0.0625W")
        (field (name "AUTHOR") "CERN DEM JLC")
      )
      (libsource (lib "Resistors") (part "Resistor - 1%"))
    )
    (comp (ref "R16")
      (value "5k6")
      (footprint "RESC1005X40N")
      (description "Resistor - 1%")
      (fields
        (field (name "PART NUMBER") "R0402_5K6_1%_0.0625W_100PPM")
        (field (name "POWER") "0.0625W")
        (field (name "AUTHOR") "CERN DEM JLC")
      )
      (libsource (lib "Resistors") (part "Resistor - 1%"))
    )
    (comp (ref "R17")
      (value "10k")
      (footprint "RESC1005X40N")
      (description "Resistor - 1%")
      (fields
        (field (name "PART NUMBER") "R0402_10K_1%_0.0625W_100PPM")
        (field (name "POWER") "0.0625W")
        (field (name "AUTHOR") "CERN DEM JLC")
      )
      (libsource (lib "Resistors") (part "Resistor - 1%"))
    )
    (comp (ref "R18")
      (value "30k")
      (footprint "RESC1608X55N")
      (description "Resistor - 1%")
      (fields
        (field (name "PART NUMBER") "R0603_30K_1%_0.1W_100PPM")
        (field (name "POWER") "0.1W")
        (field (name "AUTHOR") "CERN DEM JLC")
      )
      (libsource (lib "Resistors") (part "Resistor - 1%"))
    )
    (comp (ref "R19")
      (value "27k")
      (footprint "RESC1005X40N")
      (description "Resistor - 1%")
      (fields
        (field (name "PART NUMBER") "R0402_27K_1%_0.0625W_100PPM")
        (field (name "POWER") "0.0625W")
        (field (name "AUTHOR") "CERN DEM JLC")
      )
      (libsource (lib "Resistors") (part "Resistor - 1%"))
    )
    (comp (ref "R20")
      (value "2k4")
      (footprint "RESC1005X40N")
      (description "Resistor - 1%")
      (fields
        (field (name "PART NUMBER") "R0402_2K4_1%_0.0625W_100PPM")
        (field (name "POWER") "0.0625W")
        (field (name "AUTHOR") "CERN DEM JLC")
      )
      (libsource (lib "Resistors") (part "Resistor - 1%"))
    )
    (comp (ref "R21")
      (value "2k4")
      (footprint "RESC1005X40N")
      (description "Resistor - 1%")
      (fields
        (field (name "PART NUMBER") "R0402_2K4_1%_0.0625W_100PPM")
        (field (name "POWER") "0.0625W")
        (field (name "AUTHOR") "CERN DEM JLC")
      )
      (libsource (lib "Resistors") (part "Resistor - 1%"))
    )
    (comp (ref "R22")
      (value "3k6")
      (footprint "RESC1005X40N")
      (description "Resistor - 1%")
      (fields
        (field (name "PART NUMBER") "R0402_3K6_1%_0.0625W_100PPM")
        (field (name "POWER") "0.0625W")
        (field (name "AUTHOR") "CERN DEM JLC")
      )
      (libsource (lib "Resistors") (part "Resistor - 1%"))
    )
    (comp (ref "R23")
      (value "2k4")
      (footprint "RESC1005X40N")
      (description "Resistor - 1%")
      (fields
        (field (name "PART NUMBER") "R0402_2K4_1%_0.0625W_100PPM")
        (field (name "POWER") "0.0625W")
        (field (name "AUTHOR") "CERN DEM JLC")
      )
      (libsource (lib "Resistors") (part "Resistor - 1%"))
    )
    (comp (ref "R24")
      (value "27k")
      (footprint "RESC1005X40N")
      (description "Resistor - 1%")
      (fields
        (field (name "PART NUMBER") "R0402_27K_1%_0.0625W_100PPM")
        (field (name "POWER") "0.0625W")
        (field (name "AUTHOR") "CERN DEM JLC")
      )
      (libsource (lib "Resistors") (part "Resistor - 1%"))
    )
    (comp (ref "R125")
      (value "11k8")
      (footprint "RESC1608X55N")
      (description "Resistor - 0.1%")
      (fields
        (field (name "PART NUMBER") "R0603_11K8_0.1%_0.063W_10PPM")
        (field (name "POWER") "0.063W")
        (field (name "AUTHOR") "CERN DEM JLC")
      )
      (libsource (lib "Resistors") (part "Resistor - 0.1%"))
    )
    (comp (ref "R126")
      (value "5k62")
      (footprint "RESC1608X55N")
      (description "Resistor - 0.1%")
      (fields
        (field (name "PART NUMBER") "R0603_5K62_0.1%_0.063W_10PPM")
        (field (name "POWER") "0.063W")
        (field (name "AUTHOR") "CERN DEM JLC")
      )
      (libsource (lib "Resistors") (part "Resistor - 0.1%"))
    )
    (comp (ref "R127")
      (value "1k78")
      (footprint "RESC1608X55N")
      (description "Resistor - 0.1%")
      (fields
        (field (name "PART NUMBER") "R0603_1K78_0.1%_0.063W_10PPM")
        (field (name "POWER") "0.063W")
        (field (name "AUTHOR") "CERN DEM JLC")
      )
      (libsource (lib "Resistors") (part "Resistor - 0.1%"))
    )
    (comp (ref "R128")
      (value "10k")
      (footprint "RESC1005X40N")
      (description "Resistor - 1%")
      (fields
        (field (name "PART NUMBER") "R0402_10K_1%_0.0625W_100PPM")
        (field (name "POWER") "0.0625W")
        (field (name "AUTHOR") "CERN DEM JLC")
      )
      (libsource (lib "Resistors") (part "Resistor - 1%"))
    )
    (comp (ref "R129")
      (value "200k")
      (footprint "RESC1005X40N")
      (description "Resistor - 1%")
      (fields
        (field (name "PART NUMBER") "R0402_200K_1%_0.0625W_100PPM")
        (field (name "POWER") "0.0625W")
        (field (name "AUTHOR") "CERN DEM JLC")
      )
      (libsource (lib "Resistors") (part "Resistor - 1%"))
    )
    (comp (ref "R130")
      (value "51k")
      (footprint "RESC1005X40N")
      (description "Resistor - 1%")
      (fields
        (field (name "TOLERANCE") "±1%")
        (field (name "PART NUMBER") "R0402_51K_1%_0.0625W_100PPM")
        (field (name "POWER") "0.0625W")
        (field (name "AUTHOR") "CERN DEM JLC")
      )
      (libsource (lib "Resistors") (part "Resistor - 1%"))
    )
    (comp (ref "R131")
      (value "18k")
      (footprint "RESC1005X40N")
      (description "Resistor - 1%")
      (fields
        (field (name "PART NUMBER") "R0402_18K_1%_0.0625W_100PPM")
        (field (name "POWER") "0.0625W")
        (field (name "AUTHOR") "CERN DEM JLC")
      )
      (libsource (lib "Resistors") (part "Resistor - 1%"))
    )
    (comp (ref "R135")
      (value "150k")
      (footprint "RESC1005X40N")
      (description "Resistor - 1%")
      (fields
        (field (name "PART NUMBER") "R0402_150K_1%_0.0625W_100PPM")
        (field (name "POWER") "0.0625W")
        (field (name "AUTHOR") "CERN DEM JLC")
      )
      (libsource (lib "Resistors") (part "Resistor - 1%"))
    )
    (comp (ref "R136")
      (value "43k")
      (footprint "RESC1005X40N")
      (description "Resistor - 1%")
      (fields
        (field (name "PART NUMBER") "R0402_43K_1%_0.0625W_100PPM")
        (field (name "POWER") "0.0625W")
        (field (name "AUTHOR") "CERN DEM JLC")
      )
      (libsource (lib "Resistors") (part "Resistor - 1%"))
    )
    (comp (ref "SCREW1")
      (value "M1.6x4")
      (footprint "BOSSARD_B1.6X4/BN660_v")
      (description "Screw")
      (fields
        (field (name "PART NUMBER") "BOSSARD_B1.6X4/BN660")
        (field (name "MANUFACTURER") "BOSSARD")
        (field (name "AUTHOR") "GK")
      )
      (libsource (lib "Mechanical") (part "MECH_SCREW_M1.6x4"))
    )
    (comp (ref "SCREW2")
      (value "M1.6x4")
      (footprint "BOSSARD_B1.6X4/BN660_v")
      (description "Screw")
      (fields
        (field (name "PART NUMBER") "BOSSARD_B1.6X4/BN660")
        (field (name "MANUFACTURER") "BOSSARD")
        (field (name "AUTHOR") "GK")
      )
      (libsource (lib "Mechanical") (part "MECH_SCREW_M1.6x4"))
    )
    (comp (ref "T1")
      (value "PMGD280UN")
      (footprint "SOT65P210X110-6N")
      (description "Dual N-Channel micro TrenchMOS™ Ultra Low Level FET")
      (fields (field (name "MANUFACTURER") "NXP SEMICONDUCTORS") (field (name "AUTHOR") "CERN DEM JLC"))
      (libsource (lib "ICs And Semiconductors") (part "PMGD280UN"))
    )
    (comp (ref "TP1")
      (value "Test Point")
      (footprint "TPS127")
      (fields (field (name "PART NUMBER") "SMD_PAD_1.27X1.27MM") (field (name "AUTHOR") "CERN DEM JLC"))
      (libsource (lib "Eletro-mechanical") (part "Test Point"))
    )
    (comp (ref "TP2")
      (value "Test Point")
      (footprint "TPS127")
      (fields (field (name "PART NUMBER") "SMD_PAD_1.27X1.27MM") (field (name "AUTHOR") "CERN DEM JLC"))
      (libsource (lib "Eletro-mechanical") (part "Test Point"))
    )
    (comp (ref "TP25")
      (value "Test Point")
      (footprint "TPS127")
      (fields (field (name "PART NUMBER") "SMD_PAD_1.27X1.27MM") (field (name "AUTHOR") "CERN DEM JLC"))
      (libsource (lib "Eletro-mechanical") (part "Test Point"))
    )
    (comp (ref "TP26")
      (value "Test Point")
      (footprint "TPS127")
      (fields (field (name "PART NUMBER") "SMD_PAD_1.27X1.27MM") (field (name "AUTHOR") "CERN DEM JLC"))
      (libsource (lib "Eletro-mechanical") (part "Test Point"))
    )
    (comp (ref "TP27")
      (value "Test Point")
      (footprint "TPS127")
      (fields (field (name "PART NUMBER") "SMD_PAD_1.27X1.27MM") (field (name "AUTHOR") "CERN DEM JLC"))
      (libsource (lib "Eletro-mechanical") (part "Test Point"))
    )
    (comp (ref "TP28")
      (value "Test Point")
      (footprint "TPS127")
      (fields (field (name "PART NUMBER") "SMD_PAD_1.27X1.27MM") (field (name "AUTHOR") "CERN DEM JLC"))
      (libsource (lib "Eletro-mechanical") (part "Test Point"))
    )
    (comp (ref "TP29")
      (value "Test Point")
      (footprint "TPS127")
      (fields (field (name "PART NUMBER") "SMD_PAD_1.27X1.27MM") (field (name "AUTHOR") "CERN DEM JLC"))
      (libsource (lib "Eletro-mechanical") (part "Test Point"))
    )
    (comp (ref "TP30")
      (value "Test Point")
      (footprint "TPS127")
      (fields (field (name "PART NUMBER") "SMD_PAD_1.27X1.27MM") (field (name "AUTHOR") "CERN DEM JLC"))
      (libsource (lib "Eletro-mechanical") (part "Test Point"))
    )
    (comp (ref "TP31")
      (value "Test Point")
      (footprint "TPS127")
      (fields (field (name "PART NUMBER") "SMD_PAD_1.27X1.27MM") (field (name "AUTHOR") "CERN DEM JLC"))
      (libsource (lib "Eletro-mechanical") (part "Test Point"))
    )
    (comp (ref "TP32")
      (value "Test Point")
      (footprint "TPS127")
      (fields (field (name "PART NUMBER") "SMD_PAD_1.27X1.27MM") (field (name "AUTHOR") "CERN DEM JLC"))
      (libsource (lib "Eletro-mechanical") (part "Test Point"))
    )
    (comp (ref "TP33")
      (value "Test Point")
      (footprint "TPS127")
      (fields (field (name "PART NUMBER") "SMD_PAD_1.27X1.27MM") (field (name "AUTHOR") "CERN DEM JLC"))
      (libsource (lib "Eletro-mechanical") (part "Test Point"))
    )
    (comp (ref "TP34")
      (value "Test Point")
      (footprint "TPS127")
      (fields (field (name "PART NUMBER") "SMD_PAD_1.27X1.27MM") (field (name "AUTHOR") "CERN DEM JLC"))
      (libsource (lib "Eletro-mechanical") (part "Test Point"))
    )
  )
  (nets
    (net (code "1") (name "/N3V5") (class "Default")
      (node (ref "C266") (pin "2") (pinfunction "2_2") (pintype "passive"))
      (node (ref "C267") (pin "2") (pinfunction "2_2") (pintype "passive"))
      (node (ref "IC49") (pin "7") (pinfunction "VOUT_7") (pintype "input"))
      (node (ref "L34") (pin "2") (pinfunction "2_2") (pintype "passive"))
      (node (ref "L35") (pin "1") (pinfunction "1_1") (pintype "passive"))
    )
    (net (code "2") (name "/P2V3") (class "Default")
      (node (ref "C18") (pin "2") (pinfunction "2_2") (pintype "passive"))
      (node (ref "C261") (pin "1") (pinfunction "1_1") (pintype "passive"))
      (node (ref "L3") (pin "1") (pinfunction "1_1") (pintype "passive"))
      (node (ref "L32") (pin "2") (pinfunction "2_2") (pintype "passive"))
    )
    (net (code "3") (name "/P2V3_N") (class "Default")
      (node (ref "C231") (pin "2") (pinfunction "2_2") (pintype "passive"))
      (node (ref "L30") (pin "2") (pinfunction "2_2") (pintype "passive"))
      (node (ref "L32") (pin "1") (pinfunction "1_1") (pintype "passive"))
      (node (ref "R130") (pin "2") (pinfunction "2_2") (pintype "passive"))
    )
    (net (code "4") (name "/P3V7") (class "Default")
      (node (ref "C187") (pin "1") (pinfunction "1_1") (pintype "passive"))
      (node (ref "C6") (pin "2") (pinfunction "2_2") (pintype "passive"))
      (node (ref "L1") (pin "1") (pinfunction "1_1") (pintype "passive"))
      (node (ref "L19") (pin "2") (pinfunction "2_2") (pintype "passive"))
    )
    (net (code "5") (name "/P3V7_N") (class "Default")
      (node (ref "C4") (pin "2") (pinfunction "2_2") (pintype "passive"))
      (node (ref "C5") (pin "2") (pinfunction "2_2") (pintype "passive"))
      (node (ref "IC44") (pin "D1") (pinfunction "VOUT1_D1") (pintype "power_in"))
      (node (ref "IC44") (pin "E1") (pinfunction "VOUT1_E1") (pintype "power_in"))
      (node (ref "L19") (pin "1") (pinfunction "1_1") (pintype "passive"))
    )
    (net (code "6") (name "/P5V5") (class "Default")
      (node (ref "C13") (pin "2") (pinfunction "2_2") (pintype "passive"))
      (node (ref "C199") (pin "1") (pinfunction "1_1") (pintype "passive"))
      (node (ref "L2") (pin "1") (pinfunction "1_1") (pintype "passive"))
      (node (ref "L28") (pin "2") (pinfunction "2_2") (pintype "passive"))
    )
    (net (code "7") (name "/P5V5_N") (class "Default")
      (node (ref "C11") (pin "2") (pinfunction "2_2") (pintype "passive"))
      (node (ref "C12") (pin "2") (pinfunction "2_2") (pintype "passive"))
      (node (ref "IC44") (pin "A1") (pinfunction "VOUT2_A1") (pintype "power_in"))
      (node (ref "IC44") (pin "B1") (pinfunction "VOUT2_B1") (pintype "power_in"))
      (node (ref "L28") (pin "1") (pinfunction "1_1") (pintype "passive"))
    )
    (net (code "8") (name "/PGOOD") (class "Default")
      (node (ref "IC2") (pin "4") (pinfunction "PG_4") (pintype "output"))
      (node (ref "IC4") (pin "4") (pinfunction "PG_4") (pintype "output"))
      (node (ref "IC49") (pin "3") (pinfunction "PG_3") (pintype "output"))
      (node (ref "J6") (pin "11") (pinfunction "11_11") (pintype "bidirectional"))
    )
    (net (code "9") (name "/PG_3V7_5V5") (class "Default")
      (node (ref "IC44") (pin "B4") (pinfunction "PGOOD2_B4") (pintype "open_collector"))
      (node (ref "IC44") (pin "D4") (pinfunction "PGOOD1_D4") (pintype "open_collector"))
      (node (ref "IC46") (pin "1") (pinfunction "EN_1") (pintype "input"))
      (node (ref "R128") (pin "2") (pinfunction "2_2") (pintype "passive"))
    )
    (net (code "10") (name "/PG_DAC") (class "Default")
      (node (ref "D3") (pin "2") (pinfunction "A_2") (pintype "passive"))
      (node (ref "IC1") (pin "4") (pinfunction "PG_4") (pintype "output"))
      (node (ref "IC2") (pin "3") (pinfunction "EN/UV_3") (pintype "input"))
      (node (ref "IC3") (pin "4") (pinfunction "PG_4") (pintype "output"))
      (node (ref "IC4") (pin "3") (pinfunction "EN/UV_3") (pintype "input"))
      (node (ref "R13") (pin "1") (pinfunction "1_1") (pintype "passive"))
    )
    (net (code "11") (name "/TEMP_ALARM") (class "Default")
      (node (ref "D3") (pin "1") (pinfunction "C_1") (pintype "passive"))
      (node (ref "IC44") (pin "B2") (pinfunction "RUN2_B2") (pintype "input"))
      (node (ref "IC44") (pin "D2") (pinfunction "RUN1_D2") (pintype "input"))
      (node (ref "J6") (pin "9") (pinfunction "9_9") (pintype "bidirectional"))
    )
    (net (code "12") (name "GND") (class "Default")
      (node (ref "C1") (pin "1") (pinfunction "1_1") (pintype "passive"))
      (node (ref "C10") (pin "1") (pinfunction "1_1") (pintype "passive"))
      (node (ref "C11") (pin "1") (pinfunction "1_1") (pintype "passive"))
      (node (ref "C12") (pin "1") (pinfunction "1_1") (pintype "passive"))
      (node (ref "C13") (pin "1") (pinfunction "1_1") (pintype "passive"))
      (node (ref "C14") (pin "2") (pinfunction "2_2") (pintype "passive"))
      (node (ref "C15") (pin "1") (pinfunction "1_1") (pintype "passive"))
      (node (ref "C16") (pin "1") (pinfunction "1_1") (pintype "passive"))
      (node (ref "C17") (pin "1") (pinfunction "1_1") (pintype "passive"))
      (node (ref "C18") (pin "1") (pinfunction "1_1") (pintype "passive"))
      (node (ref "C187") (pin "2") (pinfunction "2_2") (pintype "passive"))
      (node (ref "C19") (pin "2") (pinfunction "2_2") (pintype "passive"))
      (node (ref "C190") (pin "1") (pinfunction "1_1") (pintype "passive"))
      (node (ref "C193") (pin "1") (pinfunction "1_1") (pintype "passive"))
      (node (ref "C195") (pin "1") (pinfunction "1_1") (pintype "passive"))
      (node (ref "C199") (pin "2") (pinfunction "2_2") (pintype "passive"))
      (node (ref "C2") (pin "1") (pinfunction "1_1") (pintype "passive"))
      (node (ref "C20") (pin "1") (pinfunction "1_1") (pintype "passive"))
      (node (ref "C207") (pin "1") (pinfunction "1_1") (pintype "passive"))
      (node (ref "C21") (pin "1") (pinfunction "1_1") (pintype "passive"))
      (node (ref "C22") (pin "1") (pinfunction "1_1") (pintype "passive"))
      (node (ref "C23") (pin "1") (pinfunction "1_1") (pintype "passive"))
      (node (ref "C231") (pin "1") (pinfunction "1_1") (pintype "passive"))
      (node (ref "C261") (pin "2") (pinfunction "2_2") (pintype "passive"))
      (node (ref "C264") (pin "1") (pinfunction "1_1") (pintype "passive"))
      (node (ref "C265") (pin "1") (pinfunction "1_1") (pintype "passive"))
      (node (ref "C266") (pin "1") (pinfunction "1_1") (pintype "passive"))
      (node (ref "C267") (pin "1") (pinfunction "1_1") (pintype "passive"))
      (node (ref "C268") (pin "1") (pinfunction "1_1") (pintype "passive"))
      (node (ref "C269") (pin "1") (pinfunction "1_1") (pintype "passive"))
      (node (ref "C270") (pin "1") (pinfunction "1_1") (pintype "passive"))
      (node (ref "C271") (pin "1") (pinfunction "1_1") (pintype "passive"))
      (node (ref "C272") (pin "1") (pinfunction "1_1") (pintype "passive"))
      (node (ref "C3") (pin "1") (pinfunction "1_1") (pintype "passive"))
      (node (ref "C4") (pin "1") (pinfunction "1_1") (pintype "passive"))
      (node (ref "C5") (pin "1") (pinfunction "1_1") (pintype "passive"))
      (node (ref "C6") (pin "1") (pinfunction "1_1") (pintype "passive"))
      (node (ref "C7") (pin "2") (pinfunction "2_2") (pintype "passive"))
      (node (ref "C8") (pin "1") (pinfunction "1_1") (pintype "passive"))
      (node (ref "C9") (pin "1") (pinfunction "1_1") (pintype "passive"))
      (node (ref "D1") (pin "2") (pinfunction "A_2") (pintype "passive"))
      (node (ref "D2") (pin "1") (pinfunction "C_1") (pintype "passive"))
      (node (ref "IC1") (pin "11") (pinfunction "GND_11") (pintype "power_in"))
      (node (ref "IC1") (pin "8") (pinfunction "GND_8") (pintype "power_in"))
      (node (ref "IC2") (pin "11") (pinfunction "GND_11") (pintype "power_in"))
      (node (ref "IC2") (pin "8") (pinfunction "GND_8") (pintype "power_in"))
      (node (ref "IC3") (pin "11") (pinfunction "GND_11") (pintype "power_in"))
      (node (ref "IC3") (pin "8") (pinfunction "GND_8") (pintype "power_in"))
      (node (ref "IC4") (pin "9") (pinfunction "GND_9") (pintype "power_in"))
      (node (ref "IC44") (pin "B5") (pinfunction "GND_B5") (pintype "power_in"))
      (node (ref "IC44") (pin "C1") (pinfunction "GND_C1") (pintype "power_in"))
      (node (ref "IC44") (pin "C2") (pinfunction "GND_C2") (pintype "power_in"))
      (node (ref "IC44") (pin "C5") (pinfunction "SYNC/MODE_C5") (pintype "input"))
      (node (ref "IC44") (pin "D5") (pinfunction "GND_D5") (pintype "power_in"))
      (node (ref "IC46") (pin "2") (pinfunction "GND_2") (pintype "power_in"))
      (node (ref "IC49") (pin "10") (pinfunction "GND_10") (pintype "power_in"))
      (node (ref "IC49") (pin "13") (pinfunction "EP_13") (pintype "power_in"))
      (node (ref "IC49") (pin "9") (pinfunction "GND_9") (pintype "power_in"))
      (node (ref "J6") (pin "10") (pinfunction "10_10") (pintype "bidirectional"))
      (node (ref "J6") (pin "12") (pinfunction "12_12") (pintype "bidirectional"))
      (node (ref "J6") (pin "15") (pinfunction "15_15") (pintype "bidirectional"))
      (node (ref "J6") (pin "16") (pinfunction "16_16") (pintype "bidirectional"))
      (node (ref "J6") (pin "19") (pinfunction "19_19") (pintype "bidirectional"))
      (node (ref "J6") (pin "20") (pinfunction "20_20") (pintype "bidirectional"))
      (node (ref "J6") (pin "23") (pinfunction "23_23") (pintype "bidirectional"))
      (node (ref "J6") (pin "24") (pinfunction "24_24") (pintype "bidirectional"))
      (node (ref "J6") (pin "27") (pinfunction "27_27") (pintype "bidirectional"))
      (node (ref "J6") (pin "28") (pinfunction "28_28") (pintype "bidirectional"))
      (node (ref "J6") (pin "5") (pinfunction "5_5") (pintype "bidirectional"))
      (node (ref "J6") (pin "6") (pinfunction "6_6") (pintype "bidirectional"))
      (node (ref "LD2") (pin "2") (pinfunction "A_2") (pintype "passive"))
      (node (ref "LD3") (pin "1") (pinfunction "C_1") (pintype "passive"))
      (node (ref "LD4") (pin "1") (pinfunction "C_1") (pintype "passive"))
      (node (ref "LD5") (pin "1") (pinfunction "C_1") (pintype "passive"))
      (node (ref "LD6") (pin "1") (pinfunction "C_1") (pintype "passive"))
      (node (ref "R1") (pin "1") (pinfunction "1_1") (pintype "passive"))
      (node (ref "R10") (pin "1") (pinfunction "1_1") (pintype "passive"))
      (node (ref "R12") (pin "1") (pinfunction "1_1") (pintype "passive"))
      (node (ref "R125") (pin "2") (pinfunction "2_2") (pintype "passive"))
      (node (ref "R127") (pin "2") (pinfunction "2_2") (pintype "passive"))
      (node (ref "R129") (pin "1") (pinfunction "1_1") (pintype "passive"))
      (node (ref "R131") (pin "1") (pinfunction "1_1") (pintype "passive"))
      (node (ref "R136") (pin "2") (pinfunction "2_2") (pintype "passive"))
      (node (ref "R14") (pin "1") (pinfunction "1_1") (pintype "passive"))
      (node (ref "R16") (pin "1") (pinfunction "1_1") (pintype "passive"))
      (node (ref "R17") (pin "1") (pinfunction "1_1") (pintype "passive"))
      (node (ref "R18") (pin "2") (pinfunction "2_2") (pintype "passive"))
      (node (ref "R3") (pin "1") (pinfunction "1_1") (pintype "passive"))
      (node (ref "R4") (pin "1") (pinfunction "1_1") (pintype "passive"))
      (node (ref "R5") (pin "1") (pinfunction "1_1") (pintype "passive"))
      (node (ref "R7") (pin "1") (pinfunction "1_1") (pintype "passive"))
      (node (ref "R8") (pin "1") (pinfunction "1_1") (pintype "passive"))
      (node (ref "R9") (pin "1") (pinfunction "1_1") (pintype "passive"))
      (node (ref "T1") (pin "1") (pinfunction "S_1") (pintype "passive"))
      (node (ref "TP2") (pin "1") (pinfunction "1_1") (pintype "bidirectional"))
    )
    (net (code "13") (name "N3V0A") (class "Default")
      (node (ref "C20") (pin "2") (pinfunction "2_2") (pintype "passive"))
      (node (ref "C21") (pin "2") (pinfunction "2_2") (pintype "passive"))
      (node (ref "D2") (pin "2") (pinfunction "A_2") (pintype "passive"))
      (node (ref "IC4") (pin "10") (pinfunction "OUTS_10") (pintype "output"))
      (node (ref "IC4") (pin "11") (pinfunction "OUT_11") (pintype "output"))
      (node (ref "IC4") (pin "12") (pinfunction "OUT_12") (pintype "output"))
      (node (ref "J6") (pin "7") (pinfunction "7_7") (pintype "bidirectional"))
      (node (ref "J6") (pin "8") (pinfunction "8_8") (pintype "bidirectional"))
      (node (ref "R15") (pin "2") (pinfunction "2_2") (pintype "passive"))
      (node (ref "R20") (pin "2") (pinfunction "2_2") (pintype "passive"))
      (node (ref "TP32") (pin "1") (pinfunction "1_1") (pintype "bidirectional"))
    )
    (net (code "14") (name "Net-(C8-Pad2)") (class "Default")
      (node (ref "C8") (pin "2") (pinfunction "2_2") (pintype "passive"))
      (node (ref "IC2") (pin "1") (pinfunction "IN_1") (pintype "input"))
      (node (ref "IC2") (pin "2") (pinfunction "IN_2") (pintype "input"))
      (node (ref "L2") (pin "2") (pinfunction "2_2") (pintype "passive"))
    )
    (net (code "15") (name "Net-(C22-Pad2)") (class "Default")
      (node (ref "C22") (pin "2") (pinfunction "2_2") (pintype "passive"))
      (node (ref "IC4") (pin "1") (pinfunction "IN_1") (pintype "input"))
      (node (ref "IC4") (pin "13") (pinfunction "IN_13") (pintype "power_in"))
      (node (ref "IC4") (pin "2") (pinfunction "IN_2") (pintype "input"))
      (node (ref "L36") (pin "2") (pinfunction "2_2") (pintype "passive"))
    )
    (net (code "16") (name "Net-(C268-Pad2)") (class "Default")
      (node (ref "C268") (pin "2") (pinfunction "2_2") (pintype "passive"))
      (node (ref "C269") (pin "2") (pinfunction "2_2") (pintype "passive"))
      (node (ref "L35") (pin "2") (pinfunction "2_2") (pintype "passive"))
      (node (ref "L36") (pin "1") (pinfunction "1_1") (pintype "passive"))
    )
    (net (code "17") (name "Net-(IC1-EN{slash}UV)") (class "Default")
      (node (ref "C1") (pin "2") (pinfunction "2_2") (pintype "passive"))
      (node (ref "IC1") (pin "1") (pinfunction "IN_1") (pintype "input"))
      (node (ref "IC1") (pin "2") (pinfunction "IN_2") (pintype "input"))
      (node (ref "IC1") (pin "3") (pinfunction "EN/UV_3") (pintype "input"))
      (node (ref "L1") (pin "2") (pinfunction "2_2") (pintype "passive"))
    )
    (net (code "18") (name "Net-(IC1-ILIM)") (class "Default")
      (node (ref "IC1") (pin "5") (pinfunction "ILIM_5") (pintype "input"))
      (node (ref "R3") (pin "2") (pinfunction "2_2") (pintype "passive"))
    )
    (net (code "19") (name "Net-(IC1-PGFB)") (class "Default")
      (node (ref "IC1") (pin "6") (pinfunction "PGFB_6") (pintype "input"))
      (node (ref "R1") (pin "2") (pinfunction "2_2") (pintype "passive"))
      (node (ref "R2") (pin "1") (pinfunction "1_1") (pintype "passive"))
    )
    (net (code "20") (name "Net-(IC1-SET)") (class "Default")
      (node (ref "C7") (pin "1") (pinfunction "1_1") (pintype "passive"))
      (node (ref "IC1") (pin "7") (pinfunction "SET_7") (pintype "input"))
      (node (ref "R4") (pin "2") (pinfunction "2_2") (pintype "passive"))
    )
    (net (code "21") (name "Net-(IC2-ILIM)") (class "Default")
      (node (ref "IC2") (pin "5") (pinfunction "ILIM_5") (pintype "input"))
      (node (ref "R7") (pin "2") (pinfunction "2_2") (pintype "passive"))
    )
    (net (code "22") (name "Net-(IC2-PGFB)") (class "Default")
      (node (ref "IC2") (pin "6") (pinfunction "PGFB_6") (pintype "input"))
      (node (ref "R5") (pin "2") (pinfunction "2_2") (pintype "passive"))
      (node (ref "R6") (pin "1") (pinfunction "1_1") (pintype "passive"))
    )
    (net (code "23") (name "Net-(IC2-SET)") (class "Default")
      (node (ref "C14") (pin "1") (pinfunction "1_1") (pintype "passive"))
      (node (ref "IC2") (pin "7") (pinfunction "SET_7") (pintype "input"))
      (node (ref "R8") (pin "2") (pinfunction "2_2") (pintype "passive"))
      (node (ref "R9") (pin "2") (pinfunction "2_2") (pintype "passive"))
    )
    (net (code "24") (name "Net-(IC3-EN{slash}UV)") (class "Default")
      (node (ref "C15") (pin "2") (pinfunction "2_2") (pintype "passive"))
      (node (ref "IC3") (pin "1") (pinfunction "IN_1") (pintype "input"))
      (node (ref "IC3") (pin "2") (pinfunction "IN_2") (pintype "input"))
      (node (ref "IC3") (pin "3") (pinfunction "EN/UV_3") (pintype "input"))
      (node (ref "L3") (pin "2") (pinfunction "2_2") (pintype "passive"))
    )
    (net (code "25") (name "Net-(IC3-ILIM)") (class "Default")
      (node (ref "IC3") (pin "5") (pinfunction "ILIM_5") (pintype "input"))
      (node (ref "R12") (pin "2") (pinfunction "2_2") (pintype "passive"))
    )
    (net (code "26") (name "Net-(IC3-PGFB)") (class "Default")
      (node (ref "IC3") (pin "6") (pinfunction "PGFB_6") (pintype "input"))
      (node (ref "R10") (pin "2") (pinfunction "2_2") (pintype "passive"))
      (node (ref "R11") (pin "1") (pinfunction "1_1") (pintype "passive"))
    )
    (net (code "27") (name "Net-(IC3-SET)") (class "Default")
      (node (ref "C19") (pin "1") (pinfunction "1_1") (pintype "passive"))
      (node (ref "IC3") (pin "7") (pinfunction "SET_7") (pintype "input"))
      (node (ref "R14") (pin "2") (pinfunction "2_2") (pintype "passive"))
    )
    (net (code "28") (name "Net-(IC4-ILIM)") (class "Default")
      (node (ref "IC4") (pin "6") (pinfunction "ILIM_6") (pintype "input"))
      (node (ref "R17") (pin "2") (pinfunction "2_2") (pintype "passive"))
    )
    (net (code "29") (name "Net-(IC4-PGFB)") (class "Default")
      (node (ref "IC4") (pin "5") (pinfunction "PGFB_5") (pintype "input"))
      (node (ref "R15") (pin "1") (pinfunction "1_1") (pintype "passive"))
      (node (ref "R16") (pin "2") (pinfunction "2_2") (pintype "passive"))
    )
    (net (code "30") (name "Net-(IC4-SET)") (class "Default")
      (node (ref "C23") (pin "2") (pinfunction "2_2") (pintype "passive"))
      (node (ref "IC4") (pin "8") (pinfunction "SET_8") (pintype "input"))
      (node (ref "R18") (pin "1") (pinfunction "1_1") (pintype "passive"))
    )
    (net (code "31") (name "Net-(IC44-COMP1)") (class "Default")
      (node (ref "IC44") (pin "E5") (pinfunction "COMP1_E5") (pintype "input"))
      (node (ref "TP25") (pin "1") (pinfunction "1_1") (pintype "bidirectional"))
    )
    (net (code "32") (name "Net-(IC44-COMP2)") (class "Default")
      (node (ref "IC44") (pin "A5") (pinfunction "COMP2_A5") (pintype "input"))
      (node (ref "TP26") (pin "1") (pinfunction "1_1") (pintype "bidirectional"))
    )
    (net (code "33") (name "Net-(IC44-FB1)") (class "Default")
      (node (ref "IC44") (pin "E4") (pinfunction "FB1_E4") (pintype "input"))
      (node (ref "R125") (pin "1") (pinfunction "1_1") (pintype "passive"))
    )
    (net (code "34") (name "Net-(IC44-FB2)") (class "Default")
      (node (ref "IC44") (pin "A4") (pinfunction "FB2_A4") (pintype "input"))
      (node (ref "R126") (pin "1") (pinfunction "1_1") (pintype "passive"))
    )
    (net (code "35") (name "Net-(IC44-FREQ)") (class "Default")
      (node (ref "IC44") (pin "C4") (pinfunction "FREQ_C4") (pintype "input"))
      (node (ref "R129") (pin "2") (pinfunction "2_2") (pintype "passive"))
    )
    (net (code "36") (name "Net-(IC44-INTVCC)") (class "Default")
      (node (ref "IC44") (pin "C3") (pinfunction "INTVCC_C3") (pintype "power_in"))
      (node (ref "TP27") (pin "1") (pinfunction "1_1") (pintype "bidirectional"))
    )
    (net (code "37") (name "Net-(IC44-TRACK{slash}SS1)") (class "Default")
      (node (ref "C195") (pin "2") (pinfunction "2_2") (pintype "passive"))
      (node (ref "IC44") (pin "A3") (pinfunction "TRACK/SS2_A3") (pintype "input"))
      (node (ref "IC44") (pin "E3") (pinfunction "TRACK/SS1_E3") (pintype "input"))
    )
    (net (code "38") (name "Net-(IC46-FB)") (class "Default")
      (node (ref "IC46") (pin "5") (pinfunction "FB_5") (pintype "input"))
      (node (ref "R130") (pin "1") (pinfunction "1_1") (pintype "passive"))
      (node (ref "R131") (pin "2") (pinfunction "2_2") (pintype "passive"))
    )
    (net (code "39") (name "Net-(IC46-SW)") (class "Default")
      (node (ref "IC46") (pin "3") (pinfunction "SW_3") (pintype "power_in"))
      (node (ref "L30") (pin "1") (pinfunction "1_1") (pintype "passive"))
    )
    (net (code "40") (name "Net-(IC49-CAP)") (class "Default")
      (node (ref "C270") (pin "2") (pinfunction "2_2") (pintype "passive"))
      (node (ref "IC49") (pin "6") (pinfunction "CAP_6") (pintype "output"))
    )
    (net (code "41") (name "Net-(IC49-CP)") (class "Default")
      (node (ref "C263") (pin "1") (pinfunction "1_1") (pintype "passive"))
      (node (ref "IC49") (pin "11") (pinfunction "CP_11") (pintype "output"))
    )
    (net (code "42") (name "Net-(IC49-FB)") (class "Default")
      (node (ref "IC49") (pin "5") (pinfunction "FB_5") (pintype "input"))
      (node (ref "R135") (pin "2") (pinfunction "2_2") (pintype "passive"))
      (node (ref "R136") (pin "1") (pinfunction "1_1") (pintype "passive"))
    )
    (net (code "43") (name "Net-(IC49-SW)") (class "Default")
      (node (ref "C263") (pin "2") (pinfunction "2_2") (pintype "passive"))
      (node (ref "IC49") (pin "8") (pinfunction "SW_8") (pintype "output"))
      (node (ref "L34") (pin "1") (pinfunction "1_1") (pintype "passive"))
    )
    (net (code "44") (name "Net-(IC49-VAUX)") (class "Default")
      (node (ref "C271") (pin "2") (pinfunction "2_2") (pintype "passive"))
      (node (ref "C272") (pin "2") (pinfunction "2_2") (pintype "passive"))
      (node (ref "IC49") (pin "1") (pinfunction "VAUX_1") (pintype "output"))
    )
    (net (code "45") (name "Net-(IC49-VREF)") (class "Default")
      (node (ref "IC49") (pin "4") (pinfunction "VREF_4") (pintype "output"))
      (node (ref "R135") (pin "1") (pinfunction "1_1") (pintype "passive"))
    )
    (net (code "46") (name "Net-(J6-Pad25)") (class "Default")
      (node (ref "J6") (pin "25") (pinfunction "25_25") (pintype "bidirectional"))
      (node (ref "TP33") (pin "1") (pinfunction "1_1") (pintype "bidirectional"))
    )
    (net (code "47") (name "Net-(J6-Pad26)") (class "Default")
      (node (ref "J6") (pin "26") (pinfunction "26_26") (pintype "bidirectional"))
      (node (ref "TP34") (pin "1") (pinfunction "1_1") (pintype "bidirectional"))
    )
    (net (code "48") (name "Net-(LD1-A)") (class "Default")
      (node (ref "LD1") (pin "2") (pinfunction "A_2") (pintype "passive"))
      (node (ref "R19") (pin "1") (pinfunction "1_1") (pintype "passive"))
    )
    (net (code "49") (name "Net-(LD1-C)") (class "Default")
      (node (ref "LD1") (pin "1") (pinfunction "C_1") (pintype "passive"))
      (node (ref "T1") (pin "6") (pinfunction "D_6") (pintype "passive"))
    )
    (net (code "50") (name "Net-(LD2-C)") (class "Default")
      (node (ref "LD2") (pin "1") (pinfunction "C_1") (pintype "passive"))
      (node (ref "R20") (pin "1") (pinfunction "1_1") (pintype "passive"))
    )
    (net (code "51") (name "Net-(LD3-A)") (class "Default")
      (node (ref "LD3") (pin "2") (pinfunction "A_2") (pintype "passive"))
      (node (ref "R21") (pin "1") (pinfunction "1_1") (pintype "passive"))
    )
    (net (code "52") (name "Net-(LD4-A)") (class "Default")
      (node (ref "LD4") (pin "2") (pinfunction "A_2") (pintype "passive"))
      (node (ref "R22") (pin "1") (pinfunction "1_1") (pintype "passive"))
    )
    (net (code "53") (name "Net-(LD5-A)") (class "Default")
      (node (ref "LD5") (pin "2") (pinfunction "A_2") (pintype "passive"))
      (node (ref "R23") (pin "1") (pinfunction "1_1") (pintype "passive"))
    )
    (net (code "54") (name "Net-(LD6-A)") (class "Default")
      (node (ref "LD6") (pin "2") (pinfunction "A_2") (pintype "passive"))
      (node (ref "R24") (pin "1") (pinfunction "1_1") (pintype "passive"))
    )
    (net (code "55") (name "Net-(R126-Pad2)") (class "Default")
      (node (ref "R126") (pin "2") (pinfunction "2_2") (pintype "passive"))
      (node (ref "R127") (pin "1") (pinfunction "1_1") (pintype "passive"))
    )
    (net (code "56") (name "P1V8A") (class "Default")
      (node (ref "C16") (pin "2") (pinfunction "2_2") (pintype "passive"))
      (node (ref "C17") (pin "2") (pinfunction "2_2") (pintype "passive"))
      (node (ref "IC3") (pin "10") (pinfunction "OUT_10") (pintype "output"))
      (node (ref "IC3") (pin "9") (pinfunction "OUTS_9") (pintype "output"))
      (node (ref "J6") (pin "17") (pinfunction "17_17") (pintype "bidirectional"))
      (node (ref "J6") (pin "18") (pinfunction "18_18") (pintype "bidirectional"))
      (node (ref "R11") (pin "2") (pinfunction "2_2") (pintype "passive"))
      (node (ref "T1") (pin "2") (pinfunction "G_2") (pintype "passive"))
      (node (ref "TP30") (pin "1") (pinfunction "1_1") (pintype "bidirectional"))
    )
    (net (code "57") (name "P3V3") (class "Default")
      (node (ref "C207") (pin "2") (pinfunction "2_2") (pintype "passive"))
      (node (ref "IC46") (pin "4") (pinfunction "VIN_4") (pintype "input"))
      (node (ref "J6") (pin "21") (pinfunction "21_21") (pintype "bidirectional"))
      (node (ref "J6") (pin "22") (pinfunction "22_22") (pintype "bidirectional"))
      (node (ref "R128") (pin "1") (pinfunction "1_1") (pintype "passive"))
      (node (ref "R13") (pin "2") (pinfunction "2_2") (pintype "passive"))
      (node (ref "R23") (pin "2") (pinfunction "2_2") (pintype "passive"))
      (node (ref "TP31") (pin "1") (pinfunction "1_1") (pintype "bidirectional"))
    )
    (net (code "58") (name "P3V3A") (class "Default")
      (node (ref "C2") (pin "2") (pinfunction "2_2") (pintype "passive"))
      (node (ref "C3") (pin "2") (pinfunction "2_2") (pintype "passive"))
      (node (ref "IC1") (pin "10") (pinfunction "OUT_10") (pintype "output"))
      (node (ref "IC1") (pin "9") (pinfunction "OUTS_9") (pintype "output"))
      (node (ref "J6") (pin "29") (pinfunction "29_29") (pintype "bidirectional"))
      (node (ref "J6") (pin "30") (pinfunction "30_30") (pintype "bidirectional"))
      (node (ref "R2") (pin "2") (pinfunction "2_2") (pintype "passive"))
      (node (ref "R21") (pin "2") (pinfunction "2_2") (pintype "passive"))
      (node (ref "TP29") (pin "1") (pinfunction "1_1") (pintype "bidirectional"))
    )
    (net (code "59") (name "P5V0A") (class "Default")
      (node (ref "C10") (pin "2") (pinfunction "2_2") (pintype "passive"))
      (node (ref "C9") (pin "2") (pinfunction "2_2") (pintype "passive"))
      (node (ref "D1") (pin "1") (pinfunction "C_1") (pintype "passive"))
      (node (ref "IC2") (pin "10") (pinfunction "OUT_10") (pintype "output"))
      (node (ref "IC2") (pin "9") (pinfunction "OUTS_9") (pintype "output"))
      (node (ref "J6") (pin "13") (pinfunction "13_13") (pintype "bidirectional"))
      (node (ref "J6") (pin "14") (pinfunction "14_14") (pintype "bidirectional"))
      (node (ref "R22") (pin "2") (pinfunction "2_2") (pintype "passive"))
      (node (ref "R6") (pin "2") (pinfunction "2_2") (pintype "passive"))
      (node (ref "TP28") (pin "1") (pinfunction "1_1") (pintype "bidirectional"))
    )
    (net (code "60") (name "P12V0") (class "Default")
      (node (ref "C190") (pin "2") (pinfunction "2_2") (pintype "passive"))
      (node (ref "C193") (pin "2") (pinfunction "2_2") (pintype "passive"))
      (node (ref "C264") (pin "2") (pinfunction "2_2") (pintype "passive"))
      (node (ref "C265") (pin "2") (pinfunction "2_2") (pintype "passive"))
      (node (ref "IC44") (pin "A2") (pinfunction "VIN1_A2") (pintype "power_in"))
      (node (ref "IC44") (pin "B3") (pinfunction "VIN1_B3") (pintype "power_in"))
      (node (ref "IC44") (pin "D3") (pinfunction "VIN2_D3") (pintype "power_in"))
      (node (ref "IC44") (pin "E2") (pinfunction "VIN2_E2") (pintype "power_in"))
      (node (ref "IC49") (pin "12") (pinfunction "VIN_12") (pintype "input"))
      (node (ref "IC49") (pin "2") (pinfunction "EN_2") (pintype "input"))
      (node (ref "J6") (pin "3") (pinfunction "3_3") (pintype "bidirectional"))
      (node (ref "J6") (pin "4") (pinfunction "4_4") (pintype "bidirectional"))
      (node (ref "R19") (pin "2") (pinfunction "2_2") (pintype "passive"))
      (node (ref "R24") (pin "2") (pinfunction "2_2") (pintype "passive"))
      (node (ref "TP1") (pin "1") (pinfunction "1_1") (pintype "bidirectional"))
    )
    (net (code "61") (name "unconnected-(B1-Pad1)") (class "Default")
      (node (ref "B1") (pin "1") (pinfunction "1_1") (pintype "bidirectional"))
    )
    (net (code "62") (name "unconnected-(B2-Pad1)") (class "Default")
      (node (ref "B2") (pin "1") (pinfunction "1_1") (pintype "bidirectional"))
    )
    (net (code "63") (name "unconnected-(IC4-VIOC-Pad7)") (class "Default")
      (node (ref "IC4") (pin "7") (pinfunction "VIOC_7") (pintype "input+no_connect"))
    )
    (net (code "64") (name "unconnected-(J6-Pad1)") (class "Default")
      (node (ref "J6") (pin "1") (pinfunction "1_1") (pintype "bidirectional"))
    )
    (net (code "65") (name "unconnected-(J6-Pad2)") (class "Default")
      (node (ref "J6") (pin "2") (pinfunction "2_2") (pintype "bidirectional"))
    )
  )
)
